# LVS1.net
KiCad netlist of a schematic drawn in Altium Designer
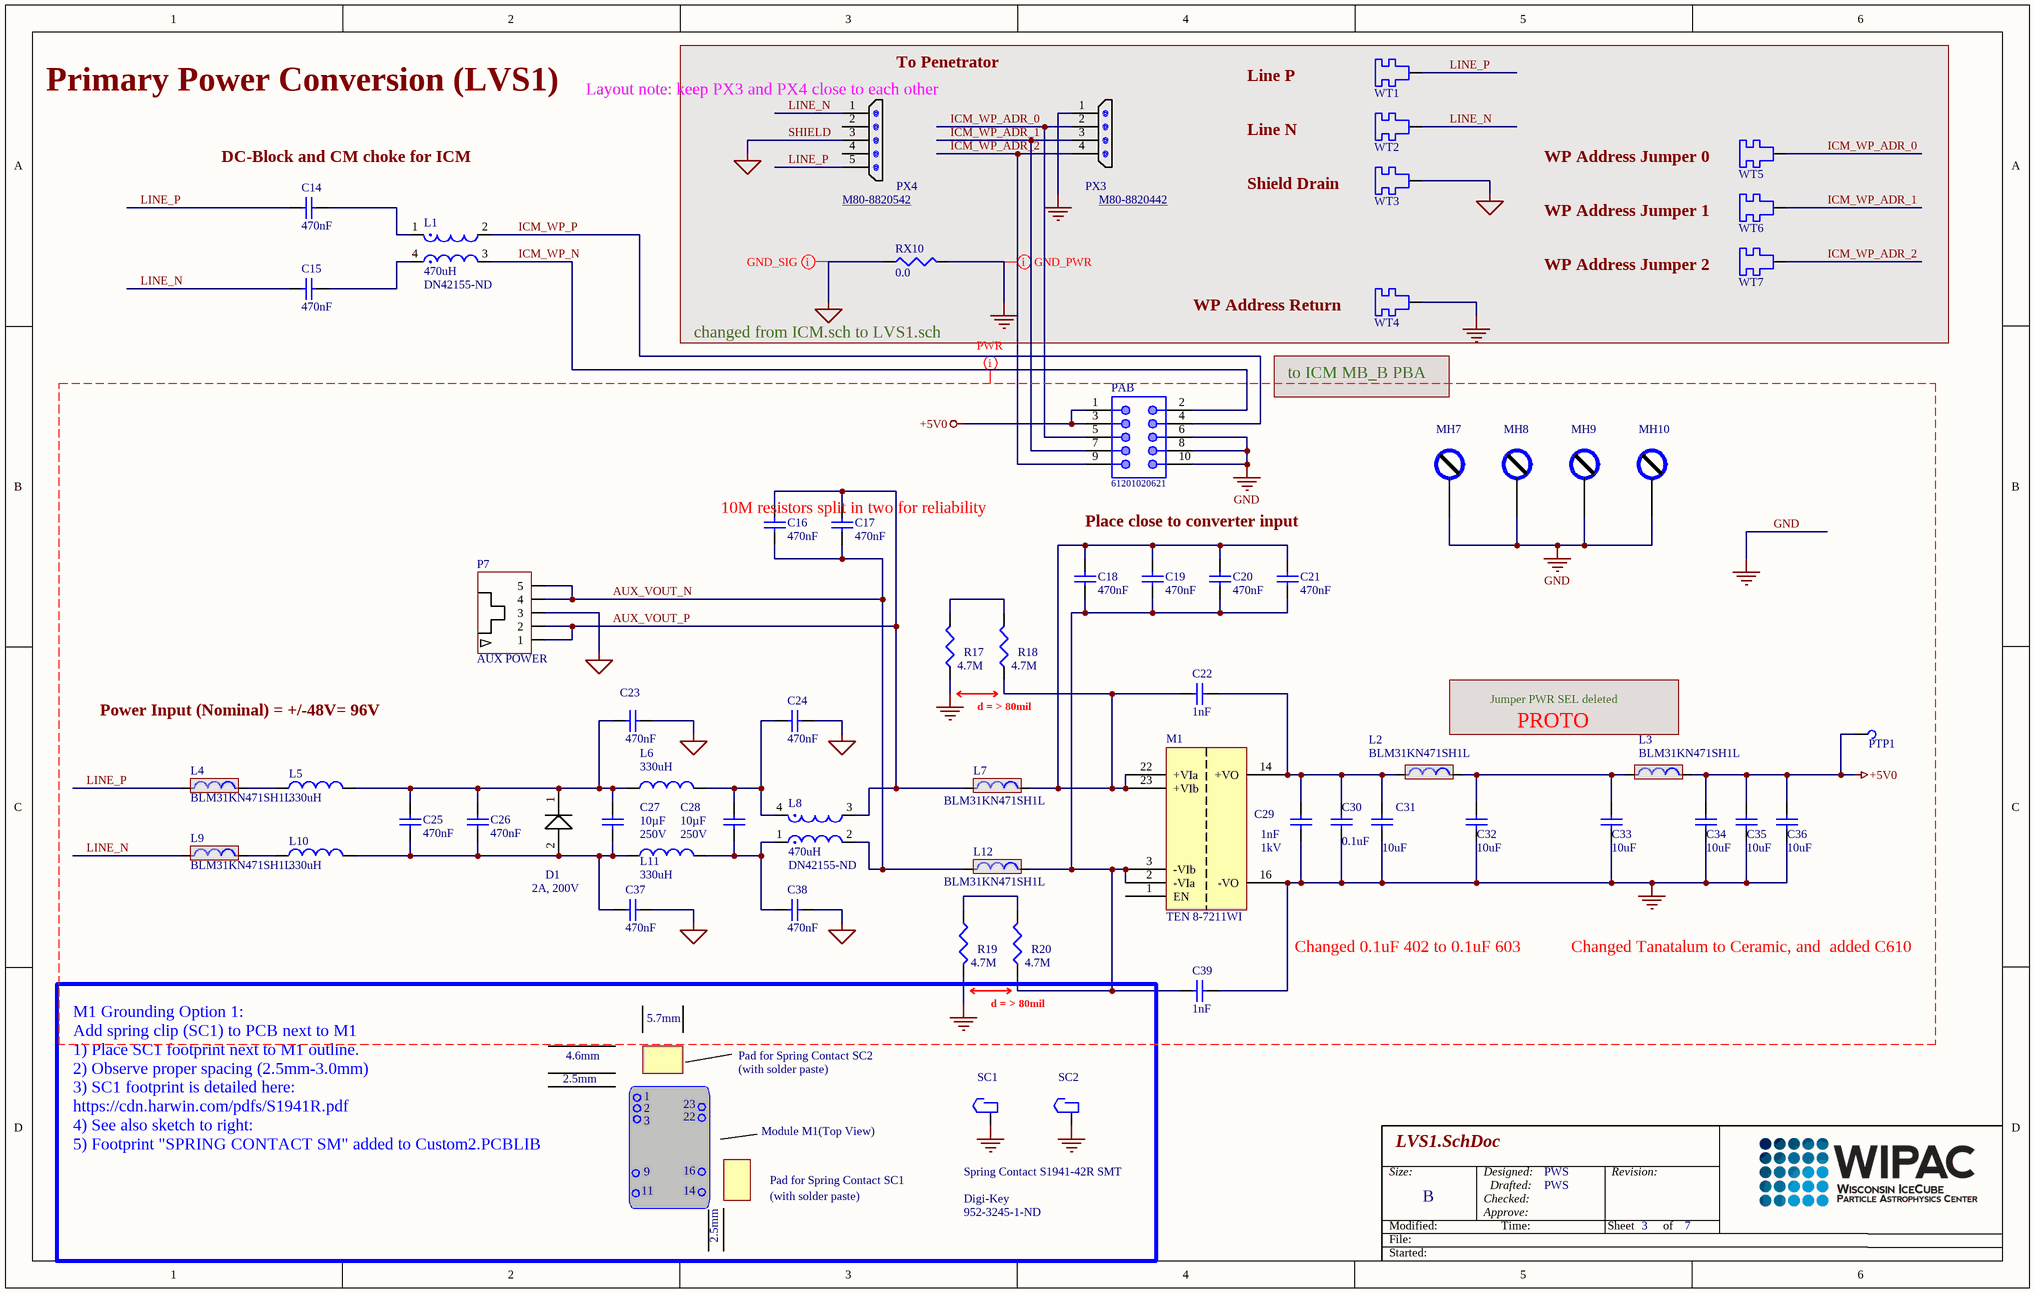
[diagram p0: LVS1.SchDoc]

(export (version "E")
  (design (tool "Eeschema 10.0.6"))
  (components
    (comp (ref "C14")
      (value "470nF_1812_450V")
      (footprint "1812")
      (description "Capacitor")
      (fields
        (field (name "MANUFACTURER") "TDK")
        (field (name "MANUFACTURER PART NUMBER") "CGA8N4X7T2W474M230KE")
        (field (name "CAPACITANCE") "470nF")
      )
      (libsource (lib "Custom1") (part "CapC_470nF_1812_450V"))
    )
    (comp (ref "C15")
      (value "470nF_1812_450V")
      (footprint "1812")
      (description "Capacitor")
      (fields
        (field (name "MANUFACTURER") "TDK")
        (field (name "MANUFACTURER PART NUMBER") "CGA8N4X7T2W474M230KE")
        (field (name "CAPACITANCE") "470nF")
      )
      (libsource (lib "Custom1") (part "CapC_470nF_1812_450V"))
    )
    (comp (ref "C16")
      (value "470nF_1812_450V")
      (footprint "1812")
      (description "Capacitor")
      (fields
        (field (name "MANUFACTURER") "TDK")
        (field (name "MANUFACTURER PART NUMBER") "CGA8N4X7T2W474M230KE")
        (field (name "CAPACITANCE") "470nF")
      )
      (libsource (lib "Custom1") (part "CapC_470nF_1812_450V"))
    )
    (comp (ref "C17")
      (value "470nF_1812_450V")
      (footprint "1812")
      (description "Capacitor")
      (fields
        (field (name "MANUFACTURER") "TDK")
        (field (name "MANUFACTURER PART NUMBER") "CGA8N4X7T2W474M230KE")
        (field (name "CAPACITANCE") "470nF")
      )
      (libsource (lib "Custom1") (part "CapC_470nF_1812_450V"))
    )
    (comp (ref "C18")
      (value "470nF_1812_450V")
      (footprint "1812")
      (description "Capacitor")
      (fields
        (field (name "MANUFACTURER") "TDK")
        (field (name "MANUFACTURER PART NUMBER") "CGA8N4X7T2W474M230KE")
        (field (name "CAPACITANCE") "470nF")
      )
      (libsource (lib "Custom1") (part "CapC_470nF_1812_450V"))
    )
    (comp (ref "C19")
      (value "470nF_1812_450V")
      (footprint "1812")
      (description "Capacitor")
      (fields
        (field (name "MANUFACTURER") "TDK")
        (field (name "MANUFACTURER PART NUMBER") "CGA8N4X7T2W474M230KE")
        (field (name "CAPACITANCE") "470nF")
      )
      (libsource (lib "Custom1") (part "CapC_470nF_1812_450V"))
    )
    (comp (ref "C20")
      (value "470nF_1812_450V")
      (footprint "1812")
      (description "Capacitor")
      (fields
        (field (name "MANUFACTURER") "TDK")
        (field (name "MANUFACTURER PART NUMBER") "CGA8N4X7T2W474M230KE")
        (field (name "CAPACITANCE") "470nF")
      )
      (libsource (lib "Custom1") (part "CapC_470nF_1812_450V"))
    )
    (comp (ref "C21")
      (value "470nF_1812_450V")
      (footprint "1812")
      (description "Capacitor")
      (fields
        (field (name "MANUFACTURER") "TDK")
        (field (name "MANUFACTURER PART NUMBER") "CGA8N4X7T2W474M230KE")
        (field (name "CAPACITANCE") "470nF")
      )
      (libsource (lib "Custom1") (part "CapC_470nF_1812_450V"))
    )
    (comp (ref "C22")
      (value "1000pF_1206_1000V")
      (footprint "CAPC_1206")
      (description "Capacitor")
      (fields
        (field (name "MANUFACTURER") "KEMET")
        (field (name "MANUFACTURER PART NUMBER") "C1206X102KDRACAUTO")
        (field (name "CAPACITANCE") "1nF")
      )
      (libsource (lib "Custom1") (part "CapC_1000pF_1206_1000V"))
    )
    (comp (ref "C23")
      (value "470nF_1812_450V")
      (footprint "1812")
      (description "Capacitor")
      (fields
        (field (name "MANUFACTURER") "TDK")
        (field (name "MANUFACTURER PART NUMBER") "CGA8N4X7T2W474M230KE")
        (field (name "CAPACITANCE") "470nF")
      )
      (libsource (lib "Custom1") (part "CapC_470nF_1812_450V"))
    )
    (comp (ref "C24")
      (value "470nF_1812_450V")
      (footprint "1812")
      (description "Capacitor")
      (fields
        (field (name "MANUFACTURER") "TDK")
        (field (name "MANUFACTURER PART NUMBER") "CGA8N4X7T2W474M230KE")
        (field (name "CAPACITANCE") "470nF")
      )
      (libsource (lib "Custom1") (part "CapC_470nF_1812_450V"))
    )
    (comp (ref "C25")
      (value "470nF_1812_450V")
      (footprint "1812")
      (description "Capacitor")
      (fields
        (field (name "MANUFACTURER") "TDK")
        (field (name "MANUFACTURER PART NUMBER") "CGA8N4X7T2W474M230KE")
        (field (name "CAPACITANCE") "470nF")
      )
      (libsource (lib "Custom1") (part "CapC_470nF_1812_450V"))
    )
    (comp (ref "C26")
      (value "470nF_1812_450V")
      (footprint "1812")
      (description "Capacitor")
      (fields
        (field (name "MANUFACTURER") "TDK")
        (field (name "MANUFACTURER PART NUMBER") "CGA8N4X7T2W474M230KE")
        (field (name "CAPACITANCE") "470nF")
      )
      (libsource (lib "Custom1") (part "CapC_470nF_1812_450V"))
    )
    (comp (ref "C27")
      (value "B32524R3106K")
      (footprint "Cap Radial 1.24\" x 0.492\" x 0.846")
      (description "CAP FILM 10UF 250V RAD")
      (fields
        (field (name "MANUFACTURER") "EPCOS Inc")
        (field (name "TOLERANCE") "±10%")
        (field (name "CAPACITANCE") "10µF")
        (field (name "VOLTAGE RATING - DC") "250V")
      )
      (libsource (lib "Custom1") (part "CAP_FILM_10UF_250V_RAD"))
    )
    (comp (ref "C28")
      (value "B32524R3106K")
      (footprint "Cap Radial 1.24\" x 0.492\" x 0.846")
      (description "CAP FILM 10UF 250V RAD")
      (fields
        (field (name "MANUFACTURER") "EPCOS Inc")
        (field (name "TOLERANCE") "±10%")
        (field (name "CAPACITANCE") "10µF")
        (field (name "VOLTAGE RATING - DC") "250V")
      )
      (libsource (lib "Custom1") (part "CAP_FILM_10UF_250V_RAD"))
    )
    (comp (ref "C29")
      (value "1000pF_1206_1000V")
      (footprint "CAPC_1206")
      (description "Capacitor")
      (fields
        (field (name "MANUFACTURER") "KEMET")
        (field (name "MANUFACTURER PART NUMBER") "C1206X102KDRACAUTO")
        (field (name "CAPACITANCE") "1nF")
        (field (name "VOLTAGE RATING (DC)") "1kV")
      )
      (libsource (lib "Custom1") (part "CapC_1000pF_1206_1000V"))
    )
    (comp (ref "C30")
      (value "0.1uF_603_50V")
      (footprint "CAPC_0603")
      (description "0.1µF ±10% 50V Ceramic Capacitor X7R 0603 (1608 Metric)")
      (fields
        (field (name "MANUFACTURER") "Murata")
        (field (name "MANUFACTURER PART NUMBER") "GCJ188R71H104KA12D")
        (field (name "CAPACITANCE") "0.1uF")
      )
      (libsource (lib "Custom1") (part "CapC_0.1uF_603_50V_GCJ"))
    )
    (comp (ref "C31")
      (value "10uF_1206_16V")
      (footprint "CAPC_1206")
      (description "Capacitor")
      (fields
        (field (name "MANUFACTURER") "Murata")
        (field (name "MANUFACTURER PART NUMBER") "GCJ31CR71C106KA15L")
        (field (name "CAPACITANCE") "10uF")
      )
      (libsource (lib "Custom1") (part "CapC_10uF_1206_16V"))
    )
    (comp (ref "C32")
      (value "10uF_1206_16V")
      (footprint "CAPC_1206")
      (description "Capacitor")
      (fields
        (field (name "MANUFACTURER") "Murata")
        (field (name "MANUFACTURER PART NUMBER") "GCJ31CR71C106KA15L")
        (field (name "CAPACITANCE") "10uF")
      )
      (libsource (lib "Custom1") (part "CapC_10uF_1206_16V"))
    )
    (comp (ref "C33")
      (value "10uF_1206_16V")
      (footprint "CAPC_1206")
      (description "Capacitor")
      (fields
        (field (name "MANUFACTURER") "Murata")
        (field (name "MANUFACTURER PART NUMBER") "GCJ31CR71C106KA15L")
        (field (name "CAPACITANCE") "10uF")
      )
      (libsource (lib "Custom1") (part "CapC_10uF_1206_16V"))
    )
    (comp (ref "C34")
      (value "10uF_1206_16V")
      (footprint "CAPC_1206")
      (description "Capacitor")
      (fields
        (field (name "MANUFACTURER") "Murata")
        (field (name "MANUFACTURER PART NUMBER") "GCJ31CR71C106KA15L")
        (field (name "CAPACITANCE") "10uF")
      )
      (libsource (lib "Custom1") (part "CapC_10uF_1206_16V"))
    )
    (comp (ref "C35")
      (value "10uF_1206_16V")
      (footprint "CAPC_1206")
      (description "Capacitor")
      (fields
        (field (name "MANUFACTURER") "Murata")
        (field (name "MANUFACTURER PART NUMBER") "GCJ31CR71C106KA15L")
        (field (name "CAPACITANCE") "10uF")
      )
      (libsource (lib "Custom1") (part "CapC_10uF_1206_16V"))
    )
    (comp (ref "C36")
      (value "10uF_1206_16V")
      (footprint "CAPC_1206")
      (description "Capacitor")
      (fields
        (field (name "MANUFACTURER") "Murata")
        (field (name "MANUFACTURER PART NUMBER") "GCJ31CR71C106KA15L")
        (field (name "CAPACITANCE") "10uF")
      )
      (libsource (lib "Custom1") (part "CapC_10uF_1206_16V"))
    )
    (comp (ref "C37")
      (value "470nF_1812_450V")
      (footprint "1812")
      (description "Capacitor")
      (fields
        (field (name "MANUFACTURER") "TDK")
        (field (name "MANUFACTURER PART NUMBER") "CGA8N4X7T2W474M230KE")
        (field (name "CAPACITANCE") "470nF")
      )
      (libsource (lib "Custom1") (part "CapC_470nF_1812_450V"))
    )
    (comp (ref "C38")
      (value "470nF_1812_450V")
      (footprint "1812")
      (description "Capacitor")
      (fields
        (field (name "MANUFACTURER") "TDK")
        (field (name "MANUFACTURER PART NUMBER") "CGA8N4X7T2W474M230KE")
        (field (name "CAPACITANCE") "470nF")
      )
      (libsource (lib "Custom1") (part "CapC_470nF_1812_450V"))
    )
    (comp (ref "C39")
      (value "1000pF_1206_1000V")
      (footprint "CAPC_1206")
      (description "Capacitor")
      (fields
        (field (name "MANUFACTURER") "KEMET")
        (field (name "MANUFACTURER PART NUMBER") "C1206X102KDRACAUTO")
        (field (name "CAPACITANCE") "1nF")
      )
      (libsource (lib "Custom1") (part "CapC_1000pF_1206_1000V"))
    )
    (comp (ref "D1")
      (value "BYG22DHE3_A/H")
      (footprint "DO-214AC")
      (description "Diode Avalanche 200V 2A Surface Mount DO-214AC (SMA)")
      (fields (field (name "MANUFACTURER") "Vishay Semiconductors") (field (name "RATINGS") "2A, 200V"))
      (libsource (lib "Custom1") (part "DIODE AVALANCHE 200V 2.0A"))
    )
    (comp (ref "L1")
      (value "470uH")
      (footprint "CM6350")
      (description "CM6350R-474")
      (fields
        (field (name "MANUFACTURER") "API Delevan Inc")
        (field (name "SUPPLIER PART NUMBER 1") "DN42155-ND")
      )
      (libsource (lib "") (part "INDUCTOR COM MODE FERR 470.0UH SMD_1"))
    )
    (comp (ref "L2")
      (value "BLM31KN471SH1L")
      (footprint "IND_1206")
      (description "470 Ohms @ 100MHz 1 Power Line Ferrite Bead 1206 (3216 Metric) 4A 20mOhm")
      (fields (field (name "MANUFACTURER") "Murata"))
      (libsource (lib "Custom1") (part "Ferrite BLM31KN471SH1L"))
    )
    (comp (ref "L3")
      (value "BLM31KN471SH1L")
      (footprint "IND_1206")
      (description "470 Ohms @ 100MHz 1 Power Line Ferrite Bead 1206 (3216 Metric) 4A 20mOhm")
      (fields (field (name "MANUFACTURER") "Murata"))
      (libsource (lib "Custom1") (part "Ferrite BLM31KN471SH1L"))
    )
    (comp (ref "L4")
      (value "BLM31KN471SH1L")
      (footprint "IND_1206")
      (description "470 Ohms @ 100MHz 1 Power Line Ferrite Bead 1206 (3216 Metric) 4A 20mOhm")
      (fields (field (name "MANUFACTURER") "Murata"))
      (libsource (lib "Custom1") (part "Ferrite BLM31KN471SH1L"))
    )
    (comp (ref "L5")
      (value "Inductor_330uH_590mA")
      (footprint "IND_SMD_2P_10.4x10.4x4.8H")
      (description "Inductor")
      (fields
        (field (name "MANUFACTURER") "TDK EPCOS")
        (field (name "MANUFACTURER PART NUMBER") "B82464G4334M000")
        (field (name "INDUCTANCE") "330uH")
      )
      (libsource (lib "Custom1") (part "Inductor_330uH_590mA"))
    )
    (comp (ref "L6")
      (value "Inductor_330uH_590mA")
      (footprint "IND_SMD_2P_10.4x10.4x4.8H")
      (description "Inductor")
      (fields
        (field (name "MANUFACTURER") "TDK EPCOS")
        (field (name "MANUFACTURER PART NUMBER") "B82464G4334M000")
        (field (name "INDUCTANCE") "330uH")
      )
      (libsource (lib "Custom1") (part "Inductor_330uH_590mA"))
    )
    (comp (ref "L7")
      (value "BLM31KN471SH1L")
      (footprint "IND_1206")
      (description "470 Ohms @ 100MHz 1 Power Line Ferrite Bead 1206 (3216 Metric) 4A 20mOhm")
      (fields (field (name "MANUFACTURER") "Murata"))
      (libsource (lib "Custom1") (part "Ferrite BLM31KN471SH1L"))
    )
    (comp (ref "L8")
      (value "470uH")
      (footprint "CM6350")
      (description "CM6350R-474")
      (fields
        (field (name "MANUFACTURER") "API Delevan Inc")
        (field (name "SUPPLIER PART NUMBER 1") "DN42155-ND")
      )
      (libsource (lib "Custom1") (part "INDUCTOR COM MODE FERR 470.0UH SMD"))
    )
    (comp (ref "L9")
      (value "BLM31KN471SH1L")
      (footprint "IND_1206")
      (description "470 Ohms @ 100MHz 1 Power Line Ferrite Bead 1206 (3216 Metric) 4A 20mOhm")
      (fields (field (name "MANUFACTURER") "Murata"))
      (libsource (lib "Custom1") (part "Ferrite BLM31KN471SH1L"))
    )
    (comp (ref "L10")
      (value "Inductor_330uH_590mA")
      (footprint "IND_SMD_2P_10.4x10.4x4.8H")
      (description "Inductor")
      (fields
        (field (name "MANUFACTURER") "TDK EPCOS")
        (field (name "MANUFACTURER PART NUMBER") "B82464G4334M000")
        (field (name "INDUCTANCE") "330uH")
      )
      (libsource (lib "Custom1") (part "Inductor_330uH_590mA"))
    )
    (comp (ref "L11")
      (value "Inductor_330uH_590mA")
      (footprint "IND_SMD_2P_10.4x10.4x4.8H")
      (description "Inductor")
      (fields
        (field (name "MANUFACTURER") "TDK EPCOS")
        (field (name "MANUFACTURER PART NUMBER") "B82464G4334M000")
        (field (name "INDUCTANCE") "330uH")
      )
      (libsource (lib "Custom1") (part "Inductor_330uH_590mA"))
    )
    (comp (ref "L12")
      (value "BLM31KN471SH1L")
      (footprint "IND_1206")
      (description "470 Ohms @ 100MHz 1 Power Line Ferrite Bead 1206 (3216 Metric) 4A 20mOhm")
      (fields (field (name "MANUFACTURER") "Murata"))
      (libsource (lib "Custom1") (part "Ferrite BLM31KN471SH1L"))
    )
    (comp (ref "M1")
      (value "TEN 8-7211WI")
      (footprint "DC_DC_24DIP_9P__V1")
      (fields
        (field (name "MANUFACTURER") "Traco Power")
        (field (name "MANUFACTURER PART NUMBER") "TEN8-7211WI")
      )
      (libsource (lib "Custom1") (part "DC-DC 24 Pin 5Vo"))
    )
    (comp (ref "MH7")
      (value "Mounting Hole")
      (footprint "Mounting Pad #4 - Standoff")
      (libsource (lib "Custom1") (part "Mounting Hole #4_Standoff"))
    )
    (comp (ref "MH8")
      (value "Mounting Hole")
      (footprint "Mounting Pad #4 - Standoff")
      (libsource (lib "Custom1") (part "Mounting Hole #4_Standoff"))
    )
    (comp (ref "MH9")
      (value "Mounting Hole")
      (footprint "Mounting Pad #4 - Standoff")
      (libsource (lib "Custom1") (part "Mounting Hole #4_Standoff"))
    )
    (comp (ref "MH10")
      (value "Mounting Hole")
      (footprint "Mounting Pad #4 - Standoff")
      (libsource (lib "Custom1") (part "Mounting Hole #4_Standoff"))
    )
    (comp (ref "P7")
      (value "AUX POWER")
      (footprint "Header Male 5 Vert")
      (description "CONN HEADER 5POS .100 VERT 30AU")
      (fields (field (name "MANUFACTURER") "Molex") (field (name "MANUFACTURER PART NUMBER") "70543-0109"))
      (libsource (lib "Custom1") (part "Header Male SL-5-VERT"))
    )
    (comp (ref "PAB")
      (value "61201020621")
      (footprint "61201020621")
      (description "Male Box Header WR-BHD, SMT, Vertical, pitch 2.54 mm, 10 pins")
      (fields (field (name "PUBLISHER") "Wurth Elektronik"))
      (libsource (lib "o162711v243 Altium_WR-BHD (rev19a)") (part "61201020621"))
    )
    (comp (ref "PTP1")
      (value "PC TEST POINT MINI SMD")
      (footprint "Test Point SM")
      (description "5019KCT-ND")
      (fields
        (field (name "MANUFACTURER") "Keystone Electronics")
        (field (name "MANUFACTURER PART NUMBER") "5019")
      )
      (libsource (lib "Custom1") (part "Test Point SM"))
    )
    (comp (ref "PX3")
      (value "Harwin 4x1 2mm")
      (footprint "HARWIN M80-8820442")
      (description "Connector Header Through Hole 4 position 0.079\" (2.00mm)  M80-8820442")
      (fields (field (name "MANUFACTURER") "Harwin") (field (name "MANUFACTURER PART NUMBER") "M80-8820442"))
      (libsource (lib "Custom1") (part "Harwin 4x1 2mm"))
    )
    (comp (ref "PX4")
      (value "Harwin 5x1 2mm")
      (footprint "HARWIN M80-8820542")
      (description "CONN HEADER VERT 5POS 2MM   M80-8820542")
      (fields (field (name "MANUFACTURER") "Harwin") (field (name "MANUFACTURER PART NUMBER") "M80-8820542"))
      (libsource (lib "Custom1") (part "Harwin 5x1 2mm"))
    )
    (comp (ref "R17")
      (value "R_4.7M_1206_1%")
      (footprint "RES_1206")
      (fields
        (field (name "MANUFACTURER") "Rohm")
        (field (name "MANUFACTURER PART NUMBER") "KTR18EZPF4704")
        (field (name "TOLERANCE") "1%")
        (field (name "RESISTANCE") "4.7M")
      )
      (libsource (lib "Custom1") (part "R_4.7M_1206_1%"))
    )
    (comp (ref "R18")
      (value "R_4.7M_1206_1%")
      (footprint "RES_1206")
      (fields
        (field (name "MANUFACTURER") "Rohm")
        (field (name "MANUFACTURER PART NUMBER") "KTR18EZPF4704")
        (field (name "TOLERANCE") "1%")
        (field (name "RESISTANCE") "4.7M")
      )
      (libsource (lib "Custom1") (part "R_4.7M_1206_1%"))
    )
    (comp (ref "R19")
      (value "R_4.7M_1206_1%")
      (footprint "RES_1206")
      (fields
        (field (name "MANUFACTURER") "Rohm")
        (field (name "MANUFACTURER PART NUMBER") "KTR18EZPF4704")
        (field (name "TOLERANCE") "1%")
        (field (name "RESISTANCE") "4.7M")
      )
      (libsource (lib "Custom1") (part "R_4.7M_1206_1%"))
    )
    (comp (ref "R20")
      (value "R_4.7M_1206_1%")
      (footprint "RES_1206")
      (fields
        (field (name "MANUFACTURER") "Rohm")
        (field (name "MANUFACTURER PART NUMBER") "KTR18EZPF4704")
        (field (name "TOLERANCE") "1%")
        (field (name "RESISTANCE") "4.7M")
      )
      (libsource (lib "Custom1") (part "R_4.7M_1206_1%"))
    )
    (comp (ref "RX10")
      (value "R_ZERO_805")
      (footprint "RES_0805")
      (description "RES ZERO OHM 0805 SMD")
      (fields
        (field (name "MANUFACTURER") "Panasonic")
        (field (name "MANUFACTURER PART NUMBER") "ERJ6GEY0R00V")
        (field (name "RESISTANCE") "0.0")
      )
      (libsource (lib "Custom1") (part "R_ZERO_805"))
    )
    (comp (ref "SC1")
      (value "Spring Contact S1941-42R SMT")
      (footprint "Spring Contact SM")
      (description "RFI SHIELD FINGER GOLD SMD")
      (fields
        (field (name "SUPPLIER 1") "Digi-Key")
        (field (name "MANUFACTURER") "Harwin")
        (field (name "MANUFACTURER PART NUMBER") "S1941-42R")
        (field (name "SUPPLIER PART NUMBER 1") "952-3245-1-ND")
      )
      (libsource (lib "Custom1") (part "Spring Contact"))
    )
    (comp (ref "SC2")
      (value "Spring Contact S1941-42R SMT")
      (footprint "Spring Contact SM")
      (description "RFI SHIELD FINGER GOLD SMD")
      (fields (field (name "MANUFACTURER") "Harwin") (field (name "MANUFACTURER PART NUMBER") "S1941-42R"))
      (libsource (lib "Custom1") (part "Spring Contact"))
    )
    (comp (ref "WT1")
      (value "Test Point Turret")
      (footprint "Turret-1592")
      (description "TERM TURRET SNG")
      (fields
        (field (name "MANUFACTURER") "Mill-Max")
        (field (name "MANUFACTURER PART NUMBER") "2506-3-00-80-00-00-07-0")
      )
      (libsource (lib "Custom1") (part "Test Point Turret"))
    )
    (comp (ref "WT2")
      (value "Test Point Turret")
      (footprint "Turret-1592")
      (description "TERM TURRET SNG")
      (fields
        (field (name "MANUFACTURER") "Mill-Max")
        (field (name "MANUFACTURER PART NUMBER") "2506-3-00-80-00-00-07-0")
      )
      (libsource (lib "Custom1") (part "Test Point Turret"))
    )
    (comp (ref "WT3")
      (value "Test Point Turret")
      (footprint "Turret-1592")
      (description "TERM TURRET SNG")
      (fields
        (field (name "MANUFACTURER") "Mill-Max")
        (field (name "MANUFACTURER PART NUMBER") "2506-3-00-80-00-00-07-0")
      )
      (libsource (lib "Custom1") (part "Test Point Turret"))
    )
    (comp (ref "WT4")
      (value "Test Point Turret")
      (footprint "Turret-1592")
      (description "TERM TURRET SNG")
      (fields
        (field (name "MANUFACTURER") "Mill-Max")
        (field (name "MANUFACTURER PART NUMBER") "2506-3-00-80-00-00-07-0")
      )
      (libsource (lib "Custom1") (part "Test Point Turret"))
    )
    (comp (ref "WT5")
      (value "Test Point Turret")
      (footprint "Turret-1592")
      (description "TERM TURRET SNG")
      (fields
        (field (name "MANUFACTURER") "Mill-Max")
        (field (name "MANUFACTURER PART NUMBER") "2506-3-00-80-00-00-07-0")
      )
      (libsource (lib "Custom1") (part "Test Point Turret"))
    )
    (comp (ref "WT6")
      (value "Test Point Turret")
      (footprint "Turret-1592")
      (description "TERM TURRET SNG")
      (fields
        (field (name "MANUFACTURER") "Mill-Max")
        (field (name "MANUFACTURER PART NUMBER") "2506-3-00-80-00-00-07-0")
      )
      (libsource (lib "Custom1") (part "Test Point Turret"))
    )
    (comp (ref "WT7")
      (value "Test Point Turret")
      (footprint "Turret-1592")
      (description "TERM TURRET SNG")
      (fields
        (field (name "MANUFACTURER") "Mill-Max")
        (field (name "MANUFACTURER PART NUMBER") "2506-3-00-80-00-00-07-0")
      )
      (libsource (lib "Custom1") (part "Test Point Turret"))
    )
  )
  (nets
    (net (code "1") (name "+5V0") (class "Default")
      (node (ref "C34") (pin "2") (pinfunction "2_2") (pintype "passive"))
      (node (ref "C35") (pin "2") (pinfunction "2_2") (pintype "passive"))
      (node (ref "C36") (pin "2") (pinfunction "2_2") (pintype "passive"))
      (node (ref "L3") (pin "2") (pinfunction "2_2") (pintype "passive"))
      (node (ref "PAB") (pin "1") (pinfunction "1_1") (pintype "passive"))
      (node (ref "PAB") (pin "3") (pinfunction "3_3") (pintype "passive"))
      (node (ref "PTP1") (pin "1") (pinfunction "1_1") (pintype "passive"))
    )
    (net (code "2") (name "/AUX_VOUT_N") (class "Default")
      (node (ref "C16") (pin "1") (pinfunction "1_1") (pintype "passive"))
      (node (ref "C17") (pin "1") (pinfunction "1_1") (pintype "passive"))
      (node (ref "L12") (pin "1") (pinfunction "1_1") (pintype "passive"))
      (node (ref "L8") (pin "2") (pinfunction "2_2") (pintype "passive"))
      (node (ref "P7") (pin "4") (pinfunction "4_4") (pintype "passive"))
      (node (ref "P7") (pin "5") (pinfunction "5_5") (pintype "passive"))
    )
    (net (code "3") (name "/AUX_VOUT_P") (class "Default")
      (node (ref "C16") (pin "2") (pinfunction "2_2") (pintype "passive"))
      (node (ref "C17") (pin "2") (pinfunction "2_2") (pintype "passive"))
      (node (ref "L7") (pin "1") (pinfunction "1_1") (pintype "passive"))
      (node (ref "L8") (pin "3") (pinfunction "3_3") (pintype "passive"))
      (node (ref "P7") (pin "1") (pinfunction "1_1") (pintype "passive"))
      (node (ref "P7") (pin "2") (pinfunction "2_2") (pintype "passive"))
    )
    (net (code "4") (name "/ICM_WP_ADR_0") (class "Default")
      (node (ref "PAB") (pin "5") (pinfunction "5_5") (pintype "passive"))
      (node (ref "PX3") (pin "2") (pinfunction "2_2") (pintype "passive"))
      (node (ref "WT5") (pin "1") (pinfunction "1_1") (pintype "passive"))
    )
    (net (code "5") (name "/ICM_WP_ADR_1") (class "Default")
      (node (ref "PAB") (pin "7") (pinfunction "7_7") (pintype "passive"))
      (node (ref "PX3") (pin "3") (pinfunction "3_3") (pintype "passive"))
      (node (ref "WT6") (pin "1") (pinfunction "1_1") (pintype "passive"))
    )
    (net (code "6") (name "/ICM_WP_ADR_2") (class "Default")
      (node (ref "PAB") (pin "9") (pinfunction "9_9") (pintype "passive"))
      (node (ref "PX3") (pin "4") (pinfunction "4_4") (pintype "passive"))
      (node (ref "WT7") (pin "1") (pinfunction "1_1") (pintype "passive"))
    )
    (net (code "7") (name "/ICM_WP_N") (class "Default")
      (node (ref "L1") (pin "3") (pinfunction "3_3") (pintype "passive"))
      (node (ref "PAB") (pin "2") (pinfunction "2_2") (pintype "passive"))
    )
    (net (code "8") (name "/ICM_WP_P") (class "Default")
      (node (ref "L1") (pin "2") (pinfunction "2_2") (pintype "passive"))
      (node (ref "PAB") (pin "4") (pinfunction "4_4") (pintype "passive"))
    )
    (net (code "9") (name "/LINE_N") (class "Default")
      (node (ref "C15") (pin "2") (pinfunction "2_2") (pintype "passive"))
      (node (ref "L9") (pin "1") (pinfunction "1_1") (pintype "passive"))
      (node (ref "PX4") (pin "1") (pinfunction "1_1") (pintype "passive"))
      (node (ref "WT2") (pin "1") (pinfunction "1_1") (pintype "passive"))
    )
    (net (code "10") (name "/LINE_P") (class "Default")
      (node (ref "C14") (pin "2") (pinfunction "2_2") (pintype "passive"))
      (node (ref "L4") (pin "1") (pinfunction "1_1") (pintype "passive"))
      (node (ref "PX4") (pin "5") (pinfunction "5_5") (pintype "passive"))
      (node (ref "WT1") (pin "1") (pinfunction "1_1") (pintype "passive"))
    )
    (net (code "11") (name "GND") (class "Default")
      (node (ref "C29") (pin "2") (pinfunction "2_2") (pintype "passive"))
      (node (ref "C30") (pin "1") (pinfunction "1_1") (pintype "passive"))
      (node (ref "C31") (pin "1") (pinfunction "1_1") (pintype "passive"))
      (node (ref "C32") (pin "1") (pinfunction "1_1") (pintype "passive"))
      (node (ref "C33") (pin "1") (pinfunction "1_1") (pintype "passive"))
      (node (ref "C34") (pin "1") (pinfunction "1_1") (pintype "passive"))
      (node (ref "C35") (pin "1") (pinfunction "1_1") (pintype "passive"))
      (node (ref "C36") (pin "1") (pinfunction "1_1") (pintype "passive"))
      (node (ref "C39") (pin "1") (pinfunction "1_1") (pintype "passive"))
      (node (ref "M1") (pin "16") (pinfunction "-VO_16") (pintype "passive"))
      (node (ref "MH10") (pin "0") (pinfunction "0_0") (pintype "passive"))
      (node (ref "MH7") (pin "0") (pinfunction "0_0") (pintype "passive"))
      (node (ref "MH8") (pin "0") (pinfunction "0_0") (pintype "passive"))
      (node (ref "MH9") (pin "0") (pinfunction "0_0") (pintype "passive"))
      (node (ref "PAB") (pin "10") (pinfunction "10_10") (pintype "passive"))
      (node (ref "PAB") (pin "6") (pinfunction "6_6") (pintype "passive"))
      (node (ref "PAB") (pin "8") (pinfunction "8_8") (pintype "passive"))
      (node (ref "PX3") (pin "1") (pinfunction "1_1") (pintype "passive"))
      (node (ref "R17") (pin "1") (pinfunction "1_1") (pintype "passive"))
      (node (ref "R19") (pin "2") (pinfunction "2_2") (pintype "passive"))
      (node (ref "RX10") (pin "2") (pinfunction "2_2") (pintype "passive"))
      (node (ref "SC1") (pin "1") (pinfunction "1_1") (pintype "passive"))
      (node (ref "SC2") (pin "1") (pinfunction "1_1") (pintype "passive"))
      (node (ref "WT4") (pin "1") (pinfunction "1_1") (pintype "passive"))
    )
    (net (code "12") (name "GND_S") (class "Default")
      (node (ref "C23") (pin "1") (pinfunction "1_1") (pintype "passive"))
      (node (ref "C24") (pin "2") (pinfunction "2_2") (pintype "passive"))
      (node (ref "C37") (pin "2") (pinfunction "2_2") (pintype "passive"))
      (node (ref "C38") (pin "2") (pinfunction "2_2") (pintype "passive"))
      (node (ref "P7") (pin "3") (pinfunction "3_3") (pintype "passive"))
      (node (ref "PX4") (pin "3") (pinfunction "3_3") (pintype "passive"))
      (node (ref "RX10") (pin "1") (pinfunction "1_1") (pintype "passive"))
      (node (ref "WT3") (pin "1") (pinfunction "1_1") (pintype "passive"))
    )
    (net (code "13") (name "Net-(C14-Pad1)") (class "Default")
      (node (ref "C14") (pin "1") (pinfunction "1_1") (pintype "passive"))
      (node (ref "L1") (pin "1") (pinfunction "1_1") (pintype "passive"))
    )
    (net (code "14") (name "Net-(C15-Pad1)") (class "Default")
      (node (ref "C15") (pin "1") (pinfunction "1_1") (pintype "passive"))
      (node (ref "L1") (pin "4") (pinfunction "4_4") (pintype "passive"))
    )
    (net (code "15") (name "Net-(C23-Pad2)") (class "Default")
      (node (ref "C23") (pin "2") (pinfunction "2_2") (pintype "passive"))
      (node (ref "C25") (pin "1") (pinfunction "1_1") (pintype "passive"))
      (node (ref "C26") (pin "1") (pinfunction "1_1") (pintype "passive"))
      (node (ref "C27") (pin "2") (pinfunction "2_2") (pintype "passive"))
      (node (ref "D1") (pin "1") (pinfunction "1_1") (pintype "passive"))
      (node (ref "L5") (pin "2") (pinfunction "2_2") (pintype "passive"))
      (node (ref "L6") (pin "1") (pinfunction "1_1") (pintype "passive"))
    )
    (net (code "16") (name "Net-(C24-Pad1)") (class "Default")
      (node (ref "C24") (pin "1") (pinfunction "1_1") (pintype "passive"))
      (node (ref "C28") (pin "2") (pinfunction "2_2") (pintype "passive"))
      (node (ref "L6") (pin "2") (pinfunction "2_2") (pintype "passive"))
      (node (ref "L8") (pin "4") (pinfunction "4_4") (pintype "passive"))
    )
    (net (code "17") (name "Net-(C25-Pad2)") (class "Default")
      (node (ref "C25") (pin "2") (pinfunction "2_2") (pintype "passive"))
      (node (ref "C26") (pin "2") (pinfunction "2_2") (pintype "passive"))
      (node (ref "C27") (pin "1") (pinfunction "1_1") (pintype "passive"))
      (node (ref "C37") (pin "1") (pinfunction "1_1") (pintype "passive"))
      (node (ref "D1") (pin "2") (pinfunction "2_2") (pintype "passive"))
      (node (ref "L10") (pin "2") (pinfunction "2_2") (pintype "passive"))
      (node (ref "L11") (pin "1") (pinfunction "1_1") (pintype "passive"))
    )
    (net (code "18") (name "Net-(C28-Pad1)") (class "Default")
      (node (ref "C28") (pin "1") (pinfunction "1_1") (pintype "passive"))
      (node (ref "C38") (pin "1") (pinfunction "1_1") (pintype "passive"))
      (node (ref "L11") (pin "2") (pinfunction "2_2") (pintype "passive"))
      (node (ref "L8") (pin "1") (pinfunction "1_1") (pintype "passive"))
    )
    (net (code "19") (name "Net-(C32-Pad2)") (class "Default")
      (node (ref "C32") (pin "2") (pinfunction "2_2") (pintype "passive"))
      (node (ref "C33") (pin "2") (pinfunction "2_2") (pintype "passive"))
      (node (ref "L2") (pin "2") (pinfunction "2_2") (pintype "passive"))
      (node (ref "L3") (pin "1") (pinfunction "1_1") (pintype "passive"))
    )
    (net (code "20") (name "Net-(L4-Pad2)") (class "Default")
      (node (ref "L4") (pin "2") (pinfunction "2_2") (pintype "passive"))
      (node (ref "L5") (pin "1") (pinfunction "1_1") (pintype "passive"))
    )
    (net (code "21") (name "Net-(L10-Pad1)") (class "Default")
      (node (ref "L10") (pin "1") (pinfunction "1_1") (pintype "passive"))
      (node (ref "L9") (pin "2") (pinfunction "2_2") (pintype "passive"))
    )
    (net (code "22") (name "Net-(M1-+VIa)") (class "Default")
      (node (ref "C18") (pin "2") (pinfunction "2_2") (pintype "passive"))
      (node (ref "C19") (pin "2") (pinfunction "2_2") (pintype "passive"))
      (node (ref "C20") (pin "2") (pinfunction "2_2") (pintype "passive"))
      (node (ref "C21") (pin "2") (pinfunction "2_2") (pintype "passive"))
      (node (ref "C22") (pin "2") (pinfunction "2_2") (pintype "passive"))
      (node (ref "L7") (pin "2") (pinfunction "2_2") (pintype "passive"))
      (node (ref "M1") (pin "22") (pinfunction "+VIa_22") (pintype "passive"))
      (node (ref "M1") (pin "23") (pinfunction "+VIb_23") (pintype "passive"))
      (node (ref "R18") (pin "1") (pinfunction "1_1") (pintype "passive"))
    )
    (net (code "23") (name "Net-(M1-+VO)") (class "Default")
      (node (ref "C22") (pin "1") (pinfunction "1_1") (pintype "passive"))
      (node (ref "C29") (pin "1") (pinfunction "1_1") (pintype "passive"))
      (node (ref "C30") (pin "2") (pinfunction "2_2") (pintype "passive"))
      (node (ref "C31") (pin "2") (pinfunction "2_2") (pintype "passive"))
      (node (ref "L2") (pin "1") (pinfunction "1_1") (pintype "passive"))
      (node (ref "M1") (pin "14") (pinfunction "+VO_14") (pintype "passive"))
    )
    (net (code "24") (name "Net-(M1--VIa)") (class "Default")
      (node (ref "C18") (pin "1") (pinfunction "1_1") (pintype "passive"))
      (node (ref "C19") (pin "1") (pinfunction "1_1") (pintype "passive"))
      (node (ref "C20") (pin "1") (pinfunction "1_1") (pintype "passive"))
      (node (ref "C21") (pin "1") (pinfunction "1_1") (pintype "passive"))
      (node (ref "C39") (pin "2") (pinfunction "2_2") (pintype "passive"))
      (node (ref "L12") (pin "2") (pinfunction "2_2") (pintype "passive"))
      (node (ref "M1") (pin "2") (pinfunction "-VIa_2") (pintype "passive"))
      (node (ref "M1") (pin "3") (pinfunction "-VIb_3") (pintype "passive"))
      (node (ref "R20") (pin "1") (pinfunction "1_1") (pintype "passive"))
    )
    (net (code "25") (name "Net-(R17-Pad2)") (class "Default")
      (node (ref "R17") (pin "2") (pinfunction "2_2") (pintype "passive"))
      (node (ref "R18") (pin "2") (pinfunction "2_2") (pintype "passive"))
    )
    (net (code "26") (name "Net-(R19-Pad1)") (class "Default")
      (node (ref "R19") (pin "1") (pinfunction "1_1") (pintype "passive"))
      (node (ref "R20") (pin "2") (pinfunction "2_2") (pintype "passive"))
    )
    (net (code "27") (name "unconnected-(M1-EN-Pad1)") (class "Default")
      (node (ref "M1") (pin "1") (pinfunction "EN_1") (pintype "passive"))
    )
    (net (code "28") (name "unconnected-(PX4-Pad2)") (class "Default")
      (node (ref "PX4") (pin "2") (pinfunction "2_2") (pintype "passive"))
    )
    (net (code "29") (name "unconnected-(PX4-Pad4)") (class "Default")
      (node (ref "PX4") (pin "4") (pinfunction "4_4") (pintype "passive"))
    )
  )
)
